# DAP_Main.net
KiCad netlist of a schematic drawn in Altium Designer
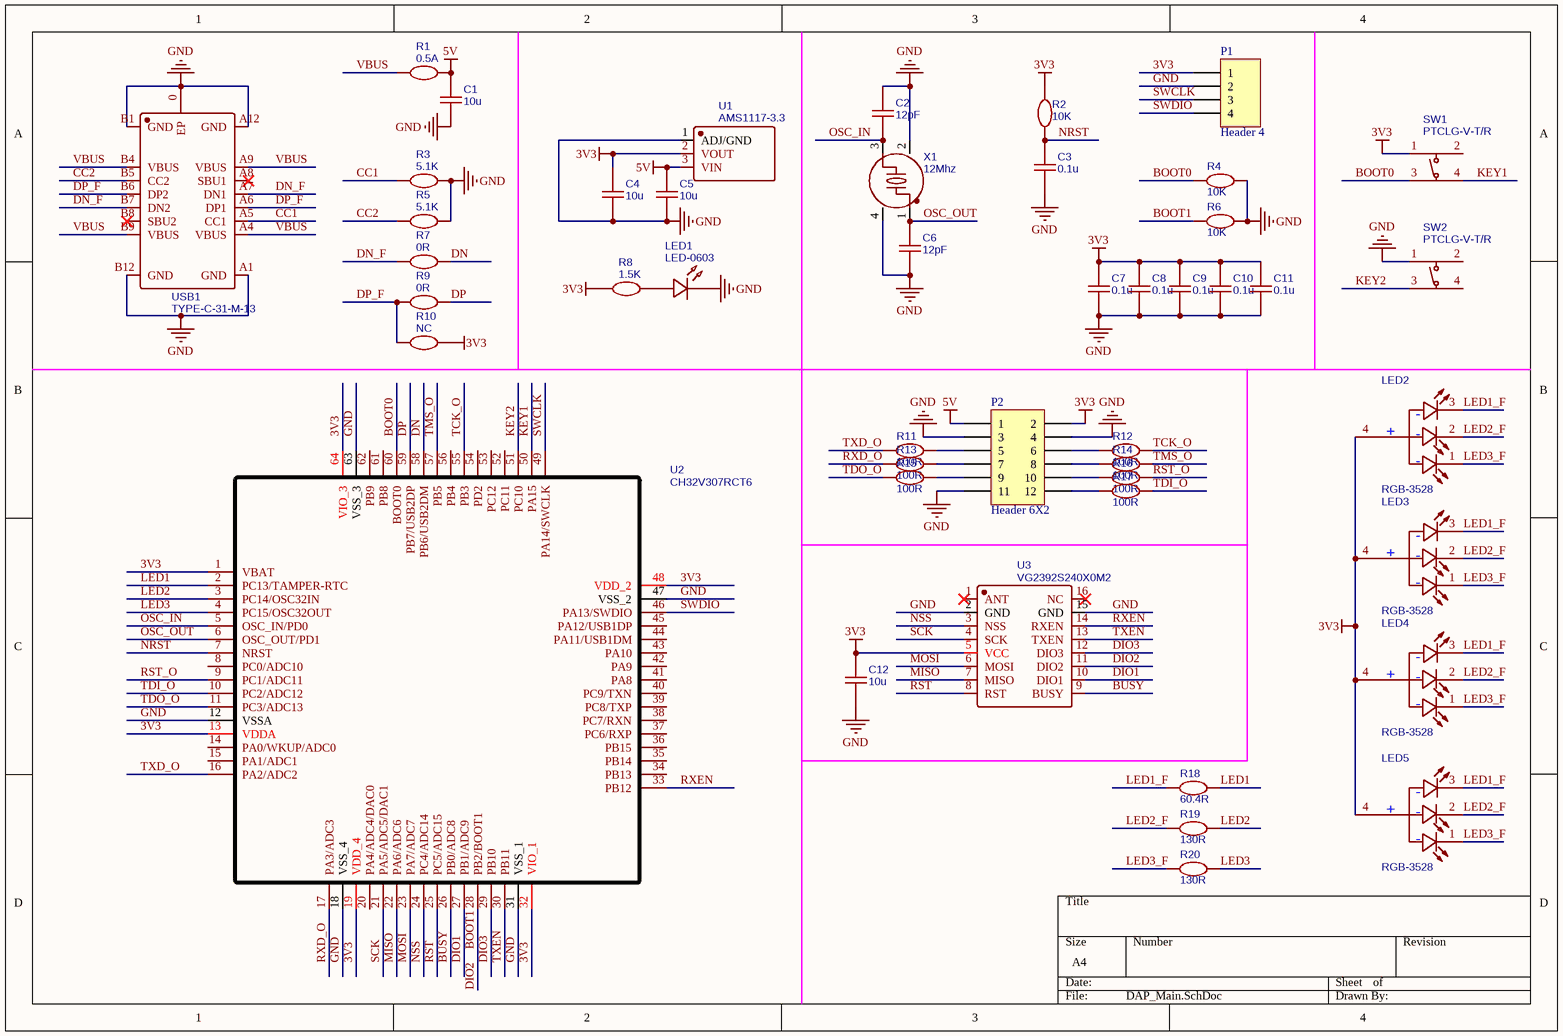
[diagram p0: DAP_Main.SchDoc]

(export (version "E")
  (design (tool "Eeschema 10.0.6"))
  (components
    (comp (ref "C1")
      (value "10u")
      (footprint "0603_CAP")
      (fields (field (name "CONTRIBUTOR") "LCEDA_Lib"))
      (libsource (lib "altium-import") (part "root_1_0.1u_"))
    )
    (comp (ref "C2")
      (value "12pF")
      (footprint "0402_CAP")
      (fields (field (name "CONTRIBUTOR") "LCEDA_Lib"))
      (libsource (lib "altium-import") (part "root_1_0.1u_"))
    )
    (comp (ref "C3")
      (value "0.1u")
      (footprint "0402_CAP")
      (fields (field (name "CONTRIBUTOR") "LCEDA_Lib"))
      (libsource (lib "altium-import") (part "root_3_0.1u_"))
    )
    (comp (ref "C4")
      (value "10u")
      (footprint "0603_CAP")
      (fields (field (name "CONTRIBUTOR") "LCEDA_Lib"))
      (libsource (lib "altium-import") (part "root_3_0.1u_"))
    )
    (comp (ref "C5")
      (value "10u")
      (footprint "0603_CAP")
      (fields (field (name "CONTRIBUTOR") "LCEDA_Lib"))
      (libsource (lib "altium-import") (part "root_1_0.1u_"))
    )
    (comp (ref "C6")
      (value "12pF")
      (footprint "0402_CAP")
      (fields (field (name "CONTRIBUTOR") "LCEDA_Lib"))
      (libsource (lib "altium-import") (part "root_1_0.1u_"))
    )
    (comp (ref "C7")
      (value "0.1u")
      (footprint "0402_CAP")
      (fields (field (name "CONTRIBUTOR") "LCEDA_Lib"))
      (libsource (lib "altium-import") (part "root_3_0.1u_"))
    )
    (comp (ref "C8")
      (value "0.1u")
      (footprint "0402_CAP")
      (fields (field (name "CONTRIBUTOR") "LCEDA_Lib"))
      (libsource (lib "altium-import") (part "root_3_0.1u_"))
    )
    (comp (ref "C9")
      (value "0.1u")
      (footprint "0402_CAP")
      (fields (field (name "CONTRIBUTOR") "LCEDA_Lib"))
      (libsource (lib "altium-import") (part "root_3_0.1u_"))
    )
    (comp (ref "C10")
      (value "0.1u")
      (footprint "0402_CAP")
      (fields (field (name "CONTRIBUTOR") "LCEDA_Lib"))
      (libsource (lib "altium-import") (part "root_3_0.1u_"))
    )
    (comp (ref "C11")
      (value "0.1u")
      (footprint "0402_CAP")
      (fields (field (name "CONTRIBUTOR") "LCEDA_Lib"))
      (libsource (lib "altium-import") (part "root_3_0.1u_"))
    )
    (comp (ref "C12")
      (value "10u")
      (footprint "0603_CAP")
      (fields (field (name "CONTRIBUTOR") "LCEDA_Lib"))
      (libsource (lib "altium-import") (part "root_3_0.1u_"))
    )
    (comp (ref "LED1")
      (value "LED-0603")
      (footprint "LED0603_RED")
      (fields
        (field (name "BOM_MANUFACTURER PART") "19-217/R6C-AL1M2VY/3T")
        (field (name "BOM_SUPPLIER PART") "C72044")
        (field (name "CONTRIBUTOR") "LCEDA_01")
      )
      (libsource (lib "altium-import") (part "root_0_LED-0603_R_"))
    )
    (comp (ref "LED2")
      (value "RGB-3528")
      (footprint "LED-ARRAY-SMD_3528-4P-L3.5-W2.8-TL-RD")
      (fields
        (field (name "BOM_SUPPLIER PART") "C264607")
        (field (name "BOM_MANUFACTURER PART") "67-23/R6GHBHC-B01/2T")
        (field (name "CONTRIBUTOR") "LCSC")
      )
      (libsource (lib "altium-import") (part "root_0_67-23/R6GHBHC-B01/2T_"))
    )
    (comp (ref "LED3")
      (value "RGB-3528")
      (footprint "LED-ARRAY-SMD_3528-4P-L3.5-W2.8-TL-RD")
      (fields
        (field (name "BOM_SUPPLIER PART") "C264607")
        (field (name "BOM_MANUFACTURER PART") "67-23/R6GHBHC-B01/2T")
        (field (name "CONTRIBUTOR") "LCSC")
      )
      (libsource (lib "altium-import") (part "root_0_67-23/R6GHBHC-B01/2T_"))
    )
    (comp (ref "LED4")
      (value "RGB-3528")
      (footprint "LED-ARRAY-SMD_3528-4P-L3.5-W2.8-TL-RD")
      (fields
        (field (name "BOM_SUPPLIER PART") "C264607")
        (field (name "BOM_MANUFACTURER PART") "67-23/R6GHBHC-B01/2T")
        (field (name "CONTRIBUTOR") "LCSC")
      )
      (libsource (lib "altium-import") (part "root_0_67-23/R6GHBHC-B01/2T_"))
    )
    (comp (ref "LED5")
      (value "RGB-3528")
      (footprint "LED-ARRAY-SMD_3528-4P-L3.5-W2.8-TL-RD")
      (fields
        (field (name "BOM_SUPPLIER PART") "C264607")
        (field (name "BOM_MANUFACTURER PART") "67-23/R6GHBHC-B01/2T")
        (field (name "CONTRIBUTOR") "LCSC")
      )
      (libsource (lib "altium-import") (part "root_0_67-23/R6GHBHC-B01/2T_"))
    )
    (comp (ref "P1")
      (value "Header 4")
      (footprint "PAD_2.54_1X4")
      (description "Header, 4-Pin")
      (fields (field (name "PUBLISHER") "Altium Limited"))
      (libsource (lib "Miscellaneous Connectors") (part "Header 4"))
    )
    (comp (ref "P2")
      (value "Header 6X2")
      (footprint "PAD_2.54_2x6_M")
      (description "Header, 6-Pin, Dual row")
      (fields (field (name "PUBLISHER") "Altium Limited"))
      (libsource (lib "Miscellaneous Connectors") (part "Header 6X2"))
    )
    (comp (ref "R1")
      (value "0.5A")
      (footprint "0603_RES")
      (fields (field (name "CONTRIBUTOR") "LCEDA_Lib"))
      (libsource (lib "altium-import") (part "root_0_1k_"))
    )
    (comp (ref "R2")
      (value "10K")
      (footprint "0402_RES")
      (fields (field (name "CONTRIBUTOR") "LCEDA_Lib"))
      (libsource (lib "altium-import") (part "root_1_1k_"))
    )
    (comp (ref "R3")
      (value "5.1K")
      (footprint "0402_RES")
      (fields (field (name "CONTRIBUTOR") "LCEDA_Lib"))
      (libsource (lib "altium-import") (part "root_0_1k_"))
    )
    (comp (ref "R4")
      (value "10K")
      (footprint "0402_RES")
      (fields (field (name "CONTRIBUTOR") "LCEDA_Lib"))
      (libsource (lib "altium-import") (part "root_2_1k_"))
    )
    (comp (ref "R5")
      (value "5.1K")
      (footprint "0402_RES")
      (fields (field (name "CONTRIBUTOR") "LCEDA_Lib"))
      (libsource (lib "altium-import") (part "root_0_1k_"))
    )
    (comp (ref "R6")
      (value "10K")
      (footprint "0402_RES")
      (fields (field (name "CONTRIBUTOR") "LCEDA_Lib"))
      (libsource (lib "altium-import") (part "root_2_1k_"))
    )
    (comp (ref "R7")
      (value "0R")
      (footprint "0402_RES")
      (fields (field (name "CONTRIBUTOR") "LCEDA_Lib"))
      (libsource (lib "altium-import") (part "root_0_1k_"))
    )
    (comp (ref "R8")
      (value "1.5K")
      (footprint "0402_RES")
      (fields (field (name "CONTRIBUTOR") "LCEDA_Lib"))
      (libsource (lib "altium-import") (part "root_0_1k_"))
    )
    (comp (ref "R9")
      (value "0R")
      (footprint "0402_RES")
      (fields (field (name "CONTRIBUTOR") "LCEDA_Lib"))
      (libsource (lib "altium-import") (part "root_0_1k_"))
    )
    (comp (ref "R10")
      (value "NC")
      (footprint "0402_RES")
      (fields (field (name "CONTRIBUTOR") "LCEDA_Lib"))
      (libsource (lib "altium-import") (part "root_0_1k_"))
    )
    (comp (ref "R11")
      (value "100R")
      (footprint "0402_RES")
      (fields (field (name "CONTRIBUTOR") "LCEDA_Lib"))
      (libsource (lib "altium-import") (part "root_0_1k_"))
    )
    (comp (ref "R12")
      (value "100R")
      (footprint "0402_RES")
      (fields (field (name "CONTRIBUTOR") "LCEDA_Lib"))
      (libsource (lib "altium-import") (part "root_0_1k_"))
    )
    (comp (ref "R13")
      (value "100R")
      (footprint "0402_RES")
      (fields (field (name "CONTRIBUTOR") "LCEDA_Lib"))
      (libsource (lib "altium-import") (part "root_0_1k_"))
    )
    (comp (ref "R14")
      (value "100R")
      (footprint "0402_RES")
      (fields (field (name "CONTRIBUTOR") "LCEDA_Lib"))
      (libsource (lib "altium-import") (part "root_0_1k_"))
    )
    (comp (ref "R15")
      (value "100R")
      (footprint "0402_RES")
      (fields (field (name "CONTRIBUTOR") "LCEDA_Lib"))
      (libsource (lib "altium-import") (part "root_0_1k_"))
    )
    (comp (ref "R16")
      (value "100R")
      (footprint "0402_RES")
      (fields (field (name "CONTRIBUTOR") "LCEDA_Lib"))
      (libsource (lib "altium-import") (part "root_0_1k_"))
    )
    (comp (ref "R17")
      (value "100R")
      (footprint "0402_RES")
      (fields (field (name "CONTRIBUTOR") "LCEDA_Lib"))
      (libsource (lib "altium-import") (part "root_0_1k_"))
    )
    (comp (ref "R18")
      (value "60.4R")
      (footprint "0603_RES")
      (fields (field (name "CONTRIBUTOR") "LCEDA_Lib"))
      (libsource (lib "altium-import") (part "root_2_1k_"))
    )
    (comp (ref "R19")
      (value "130R")
      (footprint "0603_RES")
      (fields (field (name "CONTRIBUTOR") "LCEDA_Lib"))
      (libsource (lib "altium-import") (part "root_2_1k_"))
    )
    (comp (ref "R20")
      (value "130R")
      (footprint "0603_RES")
      (fields (field (name "CONTRIBUTOR") "LCEDA_Lib"))
      (libsource (lib "altium-import") (part "root_2_1k_"))
    )
    (comp (ref "SW1")
      (value "PTCLG-V-T/R")
      (footprint "SW-SMD_4P-L4.7-W3.5-P1.70-LS5.9")
      (fields (field (name "BOM_SUPPLIER PART") "C495926") (field (name "CONTRIBUTOR") "LCSC"))
      (libsource (lib "altium-import") (part "root_0_PTCLG-V-T/R_"))
    )
    (comp (ref "SW2")
      (value "PTCLG-V-T/R")
      (footprint "SW-SMD_4P-L4.7-W3.5-P1.70-LS5.9")
      (fields (field (name "BOM_SUPPLIER PART") "C495926") (field (name "CONTRIBUTOR") "LCSC"))
      (libsource (lib "altium-import") (part "root_0_PTCLG-V-T/R_"))
    )
    (comp (ref "U1")
      (value "AMS1117-3.3")
      (footprint "SOT-89-3_L4.5-W2.5-P1.50-LS4.2-BR")
      (fields (field (name "BOM_SUPPLIER PART") "C880752") (field (name "CONTRIBUTOR") "LCSC"))
      (libsource (lib "altium-import") (part "root_0_AMS1117-3.3_"))
    )
    (comp (ref "U2")
      (value "CH32V307RCT6")
      (footprint "CH32V307RCRT6")
      (fields (field (name "CONTRIBUTOR") "lzfii"))
      (libsource (lib "altium-import") (part "root_3_CH32V307RCT6_"))
    )
    (comp (ref "U3")
      (value "VG2392S240X0M2")
      (footprint "WIRELM-SMD_16P-L24.0-W16.0-P2.00_VG2392S240X0M2")
      (fields (field (name "BOM_SUPPLIER PART") "C2976523") (field (name "CONTRIBUTOR") "lcsc"))
      (libsource (lib "altium-import") (part "root_0_VG2392S240X0M2_"))
    )
    (comp (ref "USB1")
      (value "TYPE-C-31-M-13")
      (footprint "USB-C-SMD_TYPE-C-31-M-13")
      (fields (field (name "BOM_SUPPLIER PART") "C223906") (field (name "CONTRIBUTOR") "LCSC"))
      (libsource (lib "altium-import") (part "root_0_TYPE-C-31-M-13_"))
    )
    (comp (ref "X1")
      (value "12Mhz")
      (footprint "XTAL3225")
      (fields
        (field (name "BOM_SUPPLIER PART") "C2682774")
        (field (name "BOM_MANUFACTURER PART") "X32258MSB4SI")
        (field (name "CONTRIBUTOR") "LCSC")
      )
      (libsource (lib "altium-import") (part "root_1_8MHz_"))
    )
  )
  (nets
    (net (code "1") (name "/BOOT0") (class "Default")
      (node (ref "R4") (pin "2") (pinfunction "2_2") (pintype "passive"))
      (node (ref "SW1") (pin "3") (pinfunction "3_3") (pintype "passive"))
      (node (ref "U2") (pin "60") (pinfunction "BOOT0_60") (pintype "passive"))
    )
    (net (code "2") (name "/BOOT1") (class "Default")
      (node (ref "R6") (pin "2") (pinfunction "2_2") (pintype "passive"))
      (node (ref "U2") (pin "28") (pinfunction "PB2/BOOT1_28") (pintype "passive"))
      (node (ref "U3") (pin "11") (pinfunction "DIO2_11") (pintype "passive"))
    )
    (net (code "3") (name "/BUSY") (class "Default")
      (node (ref "U2") (pin "26") (pinfunction "PB0/ADC8_26") (pintype "passive"))
      (node (ref "U3") (pin "9") (pinfunction "BUSY_9") (pintype "passive"))
    )
    (net (code "4") (name "/CC1") (class "Default")
      (node (ref "R3") (pin "1") (pinfunction "1_1") (pintype "passive"))
      (node (ref "USB1") (pin "A5") (pinfunction "CC1_A5") (pintype "passive"))
    )
    (net (code "5") (name "/CC2") (class "Default")
      (node (ref "R5") (pin "1") (pinfunction "1_1") (pintype "passive"))
      (node (ref "USB1") (pin "B5") (pinfunction "CC2_B5") (pintype "passive"))
    )
    (net (code "6") (name "/DIO1") (class "Default")
      (node (ref "U2") (pin "27") (pinfunction "PB1/ADC9_27") (pintype "passive"))
      (node (ref "U3") (pin "10") (pinfunction "DIO1_10") (pintype "passive"))
    )
    (net (code "7") (name "/DIO3") (class "Default")
      (node (ref "U2") (pin "29") (pinfunction "PB10_29") (pintype "passive"))
      (node (ref "U3") (pin "12") (pinfunction "DIO3_12") (pintype "passive"))
    )
    (net (code "8") (name "/DN") (class "Default")
      (node (ref "R7") (pin "2") (pinfunction "2_2") (pintype "passive"))
      (node (ref "U2") (pin "58") (pinfunction "PB6/USB2DM_58") (pintype "passive"))
    )
    (net (code "9") (name "/DN_F") (class "Default")
      (node (ref "R7") (pin "1") (pinfunction "1_1") (pintype "passive"))
      (node (ref "USB1") (pin "A7") (pinfunction "DN1_A7") (pintype "passive"))
      (node (ref "USB1") (pin "B7") (pinfunction "DN2_B7") (pintype "passive"))
    )
    (net (code "10") (name "/DP") (class "Default")
      (node (ref "R9") (pin "2") (pinfunction "2_2") (pintype "passive"))
      (node (ref "U2") (pin "59") (pinfunction "PB7/USB2DP_59") (pintype "passive"))
    )
    (net (code "11") (name "/DP_F") (class "Default")
      (node (ref "R10") (pin "1") (pinfunction "1_1") (pintype "passive"))
      (node (ref "R9") (pin "1") (pinfunction "1_1") (pintype "passive"))
      (node (ref "USB1") (pin "A6") (pinfunction "DP1_A6") (pintype "passive"))
      (node (ref "USB1") (pin "B6") (pinfunction "DP2_B6") (pintype "passive"))
    )
    (net (code "12") (name "/KEY1") (class "Default")
      (node (ref "SW1") (pin "4") (pinfunction "4_4") (pintype "passive"))
      (node (ref "U2") (pin "50") (pinfunction "PA15_50") (pintype "passive"))
    )
    (net (code "13") (name "/KEY2") (class "Default")
      (node (ref "SW2") (pin "3") (pinfunction "3_3") (pintype "passive"))
      (node (ref "U2") (pin "51") (pinfunction "PC10_51") (pintype "passive"))
    )
    (net (code "14") (name "/LED1") (class "Default")
      (node (ref "R18") (pin "1") (pinfunction "1_1") (pintype "passive"))
      (node (ref "U2") (pin "2") (pinfunction "PC13/TAMPER-RTC_2") (pintype "passive"))
    )
    (net (code "15") (name "/LED1_F") (class "Default")
      (node (ref "LED2") (pin "3") (pinfunction "3_3") (pintype "passive"))
      (node (ref "LED3") (pin "3") (pinfunction "3_3") (pintype "passive"))
      (node (ref "LED4") (pin "3") (pinfunction "3_3") (pintype "passive"))
      (node (ref "LED5") (pin "3") (pinfunction "3_3") (pintype "passive"))
      (node (ref "R18") (pin "2") (pinfunction "2_2") (pintype "passive"))
    )
    (net (code "16") (name "/LED2") (class "Default")
      (node (ref "R19") (pin "1") (pinfunction "1_1") (pintype "passive"))
      (node (ref "U2") (pin "3") (pinfunction "PC14/OSC32IN_3") (pintype "passive"))
    )
    (net (code "17") (name "/LED2_F") (class "Default")
      (node (ref "LED2") (pin "2") (pinfunction "2_2") (pintype "passive"))
      (node (ref "LED3") (pin "2") (pinfunction "2_2") (pintype "passive"))
      (node (ref "LED4") (pin "2") (pinfunction "2_2") (pintype "passive"))
      (node (ref "LED5") (pin "2") (pinfunction "2_2") (pintype "passive"))
      (node (ref "R19") (pin "2") (pinfunction "2_2") (pintype "passive"))
    )
    (net (code "18") (name "/LED3") (class "Default")
      (node (ref "R20") (pin "1") (pinfunction "1_1") (pintype "passive"))
      (node (ref "U2") (pin "4") (pinfunction "PC15/OSC32OUT_4") (pintype "passive"))
    )
    (net (code "19") (name "/LED3_F") (class "Default")
      (node (ref "LED2") (pin "1") (pinfunction "1_1") (pintype "passive"))
      (node (ref "LED3") (pin "1") (pinfunction "1_1") (pintype "passive"))
      (node (ref "LED4") (pin "1") (pinfunction "1_1") (pintype "passive"))
      (node (ref "LED5") (pin "1") (pinfunction "1_1") (pintype "passive"))
      (node (ref "R20") (pin "2") (pinfunction "2_2") (pintype "passive"))
    )
    (net (code "20") (name "/MISO") (class "Default")
      (node (ref "U2") (pin "22") (pinfunction "PA6/ADC6_22") (pintype "passive"))
      (node (ref "U3") (pin "7") (pinfunction "MISO_7") (pintype "passive"))
    )
    (net (code "21") (name "/MOSI") (class "Default")
      (node (ref "U2") (pin "23") (pinfunction "PA7/ADC7_23") (pintype "passive"))
      (node (ref "U3") (pin "6") (pinfunction "MOSI_6") (pintype "passive"))
    )
    (net (code "22") (name "/NRST") (class "Default")
      (node (ref "C3") (pin "1") (pinfunction "1_1") (pintype "passive"))
      (node (ref "R2") (pin "1") (pinfunction "1_1") (pintype "passive"))
      (node (ref "U2") (pin "7") (pinfunction "NRST_7") (pintype "passive"))
    )
    (net (code "23") (name "/NSS") (class "Default")
      (node (ref "U2") (pin "24") (pinfunction "PC4/ADC14_24") (pintype "passive"))
      (node (ref "U3") (pin "3") (pinfunction "NSS_3") (pintype "passive"))
    )
    (net (code "24") (name "/OSC_IN") (class "Default")
      (node (ref "C2") (pin "1") (pinfunction "1_1") (pintype "passive"))
      (node (ref "U2") (pin "5") (pinfunction "OSC_IN/PD0_5") (pintype "passive"))
      (node (ref "X1") (pin "3") (pinfunction "3_3") (pintype "passive"))
    )
    (net (code "25") (name "/OSC_OUT") (class "Default")
      (node (ref "C6") (pin "2") (pinfunction "2_2") (pintype "passive"))
      (node (ref "U2") (pin "6") (pinfunction "OSC_OUT/PD1_6") (pintype "passive"))
      (node (ref "X1") (pin "1") (pinfunction "1_1") (pintype "passive"))
    )
    (net (code "26") (name "/RST") (class "Default")
      (node (ref "U2") (pin "25") (pinfunction "PC5/ADC15_25") (pintype "passive"))
      (node (ref "U3") (pin "8") (pinfunction "RST_8") (pintype "passive"))
    )
    (net (code "27") (name "/RST_O") (class "Default")
      (node (ref "R16") (pin "2") (pinfunction "2_2") (pintype "passive"))
      (node (ref "U2") (pin "9") (pinfunction "PC1/ADC11_9") (pintype "passive"))
    )
    (net (code "28") (name "/RXD_O") (class "Default")
      (node (ref "R13") (pin "1") (pinfunction "1_1") (pintype "passive"))
      (node (ref "U2") (pin "17") (pinfunction "PA3/ADC3_17") (pintype "passive"))
    )
    (net (code "29") (name "/RXEN") (class "Default")
      (node (ref "U2") (pin "33") (pinfunction "PB12_33") (pintype "passive"))
      (node (ref "U3") (pin "14") (pinfunction "RXEN_14") (pintype "passive"))
    )
    (net (code "30") (name "/SCK") (class "Default")
      (node (ref "U2") (pin "21") (pinfunction "PA5/ADC5/DAC1_21") (pintype "passive"))
      (node (ref "U3") (pin "4") (pinfunction "SCK_4") (pintype "passive"))
    )
    (net (code "31") (name "/SWCLK") (class "Default")
      (node (ref "P1") (pin "3") (pinfunction "3_3") (pintype "passive"))
      (node (ref "U2") (pin "49") (pinfunction "PA14/SWCLK_49") (pintype "passive"))
    )
    (net (code "32") (name "/SWDIO") (class "Default")
      (node (ref "P1") (pin "4") (pinfunction "4_4") (pintype "passive"))
      (node (ref "U2") (pin "46") (pinfunction "PA13/SWDIO_46") (pintype "passive"))
    )
    (net (code "33") (name "/TCK_O") (class "Default")
      (node (ref "R12") (pin "2") (pinfunction "2_2") (pintype "passive"))
      (node (ref "U2") (pin "55") (pinfunction "PB3_55") (pintype "passive"))
    )
    (net (code "34") (name "/TDI_O") (class "Default")
      (node (ref "R17") (pin "2") (pinfunction "2_2") (pintype "passive"))
      (node (ref "U2") (pin "10") (pinfunction "PC2/ADC12_10") (pintype "passive"))
    )
    (net (code "35") (name "/TDO_O") (class "Default")
      (node (ref "R15") (pin "1") (pinfunction "1_1") (pintype "passive"))
      (node (ref "U2") (pin "11") (pinfunction "PC3/ADC13_11") (pintype "passive"))
    )
    (net (code "36") (name "/TMS_O") (class "Default")
      (node (ref "R14") (pin "2") (pinfunction "2_2") (pintype "passive"))
      (node (ref "U2") (pin "57") (pinfunction "PB5_57") (pintype "passive"))
    )
    (net (code "37") (name "/TXD_O") (class "Default")
      (node (ref "R11") (pin "1") (pinfunction "1_1") (pintype "passive"))
      (node (ref "U2") (pin "16") (pinfunction "PA2/ADC2_16") (pintype "passive"))
    )
    (net (code "38") (name "/TXEN") (class "Default")
      (node (ref "U2") (pin "30") (pinfunction "PB11_30") (pintype "passive"))
      (node (ref "U3") (pin "13") (pinfunction "TXEN_13") (pintype "passive"))
    )
    (net (code "39") (name "/VBUS") (class "Default")
      (node (ref "R1") (pin "1") (pinfunction "1_1") (pintype "passive"))
      (node (ref "USB1") (pin "A4") (pinfunction "VBUS_A4") (pintype "passive"))
      (node (ref "USB1") (pin "A9") (pinfunction "VBUS_A9") (pintype "passive"))
      (node (ref "USB1") (pin "B4") (pinfunction "VBUS_B4") (pintype "passive"))
      (node (ref "USB1") (pin "B9") (pinfunction "VBUS_B9") (pintype "passive"))
    )
    (net (code "40") (name "3V3") (class "Default")
      (node (ref "C10") (pin "1") (pinfunction "1_1") (pintype "passive"))
      (node (ref "C11") (pin "1") (pinfunction "1_1") (pintype "passive"))
      (node (ref "C12") (pin "1") (pinfunction "1_1") (pintype "passive"))
      (node (ref "C4") (pin "1") (pinfunction "1_1") (pintype "passive"))
      (node (ref "C7") (pin "1") (pinfunction "1_1") (pintype "passive"))
      (node (ref "C8") (pin "1") (pinfunction "1_1") (pintype "passive"))
      (node (ref "C9") (pin "1") (pinfunction "1_1") (pintype "passive"))
      (node (ref "LED2") (pin "4") (pinfunction "4_4") (pintype "passive"))
      (node (ref "LED3") (pin "4") (pinfunction "4_4") (pintype "passive"))
      (node (ref "LED4") (pin "4") (pinfunction "4_4") (pintype "passive"))
      (node (ref "LED5") (pin "4") (pinfunction "4_4") (pintype "passive"))
      (node (ref "P1") (pin "1") (pinfunction "1_1") (pintype "passive"))
      (node (ref "P2") (pin "2") (pinfunction "2_2") (pintype "passive"))
      (node (ref "R10") (pin "2") (pinfunction "2_2") (pintype "passive"))
      (node (ref "R2") (pin "2") (pinfunction "2_2") (pintype "passive"))
      (node (ref "R8") (pin "1") (pinfunction "1_1") (pintype "passive"))
      (node (ref "SW1") (pin "1") (pinfunction "1_1") (pintype "passive"))
      (node (ref "U1") (pin "2") (pinfunction "VOUT_2") (pintype "passive"))
      (node (ref "U2") (pin "1") (pinfunction "VBAT_1") (pintype "passive"))
      (node (ref "U2") (pin "13") (pinfunction "VDDA_13") (pintype "passive"))
      (node (ref "U2") (pin "19") (pinfunction "VDD_4_19") (pintype "passive"))
      (node (ref "U2") (pin "32") (pinfunction "VIO_1_32") (pintype "passive"))
      (node (ref "U2") (pin "48") (pinfunction "VDD_2_48") (pintype "passive"))
      (node (ref "U2") (pin "64") (pinfunction "VIO_3_64") (pintype "passive"))
      (node (ref "U3") (pin "5") (pinfunction "VCC_5") (pintype "passive"))
    )
    (net (code "41") (name "5V") (class "Default")
      (node (ref "C1") (pin "2") (pinfunction "2_2") (pintype "passive"))
      (node (ref "C5") (pin "2") (pinfunction "2_2") (pintype "passive"))
      (node (ref "P2") (pin "1") (pinfunction "1_1") (pintype "passive"))
      (node (ref "R1") (pin "2") (pinfunction "2_2") (pintype "passive"))
      (node (ref "U1") (pin "3") (pinfunction "VIN_3") (pintype "passive"))
    )
    (net (code "42") (name "GND") (class "Default")
      (node (ref "C1") (pin "1") (pinfunction "1_1") (pintype "passive"))
      (node (ref "C10") (pin "2") (pinfunction "2_2") (pintype "passive"))
      (node (ref "C11") (pin "2") (pinfunction "2_2") (pintype "passive"))
      (node (ref "C12") (pin "2") (pinfunction "2_2") (pintype "passive"))
      (node (ref "C2") (pin "2") (pinfunction "2_2") (pintype "passive"))
      (node (ref "C3") (pin "2") (pinfunction "2_2") (pintype "passive"))
      (node (ref "C4") (pin "2") (pinfunction "2_2") (pintype "passive"))
      (node (ref "C5") (pin "1") (pinfunction "1_1") (pintype "passive"))
      (node (ref "C6") (pin "1") (pinfunction "1_1") (pintype "passive"))
      (node (ref "C7") (pin "2") (pinfunction "2_2") (pintype "passive"))
      (node (ref "C8") (pin "2") (pinfunction "2_2") (pintype "passive"))
      (node (ref "C9") (pin "2") (pinfunction "2_2") (pintype "passive"))
      (node (ref "LED1") (pin "2") (pinfunction "2_2") (pintype "passive"))
      (node (ref "P1") (pin "2") (pinfunction "2_2") (pintype "passive"))
      (node (ref "P2") (pin "11") (pinfunction "11_11") (pintype "passive"))
      (node (ref "P2") (pin "3") (pinfunction "3_3") (pintype "passive"))
      (node (ref "P2") (pin "4") (pinfunction "4_4") (pintype "passive"))
      (node (ref "R3") (pin "2") (pinfunction "2_2") (pintype "passive"))
      (node (ref "R4") (pin "1") (pinfunction "1_1") (pintype "passive"))
      (node (ref "R5") (pin "2") (pinfunction "2_2") (pintype "passive"))
      (node (ref "R6") (pin "1") (pinfunction "1_1") (pintype "passive"))
      (node (ref "SW2") (pin "1") (pinfunction "1_1") (pintype "passive"))
      (node (ref "U1") (pin "1") (pinfunction "ADJ/GND_1") (pintype "passive"))
      (node (ref "U2") (pin "12") (pinfunction "VSSA_12") (pintype "passive"))
      (node (ref "U2") (pin "18") (pinfunction "VSS_4_18") (pintype "passive"))
      (node (ref "U2") (pin "31") (pinfunction "VSS_1_31") (pintype "passive"))
      (node (ref "U2") (pin "47") (pinfunction "VSS_2_47") (pintype "passive"))
      (node (ref "U2") (pin "63") (pinfunction "VSS_3_63") (pintype "passive"))
      (node (ref "U3") (pin "15") (pinfunction "GND_15") (pintype "passive"))
      (node (ref "U3") (pin "2") (pinfunction "GND_2") (pintype "passive"))
      (node (ref "USB1") (pin "0") (pinfunction "EP_0") (pintype "passive"))
      (node (ref "USB1") (pin "A1") (pinfunction "GND_A1") (pintype "passive"))
      (node (ref "USB1") (pin "A12") (pinfunction "GND_A12") (pintype "passive"))
      (node (ref "USB1") (pin "B1") (pinfunction "GND_B1") (pintype "passive"))
      (node (ref "USB1") (pin "B12") (pinfunction "GND_B12") (pintype "passive"))
      (node (ref "X1") (pin "2") (pinfunction "GND_2") (pintype "passive"))
      (node (ref "X1") (pin "4") (pinfunction "GND_4") (pintype "passive"))
    )
    (net (code "43") (name "Net-(LED1-Pad1)") (class "Default")
      (node (ref "LED1") (pin "1") (pinfunction "1_1") (pintype "passive"))
      (node (ref "R8") (pin "2") (pinfunction "2_2") (pintype "passive"))
    )
    (net (code "44") (name "Net-(P2-Pad5)") (class "Default")
      (node (ref "P2") (pin "5") (pinfunction "5_5") (pintype "passive"))
      (node (ref "R11") (pin "2") (pinfunction "2_2") (pintype "passive"))
    )
    (net (code "45") (name "Net-(P2-Pad6)") (class "Default")
      (node (ref "P2") (pin "6") (pinfunction "6_6") (pintype "passive"))
      (node (ref "R12") (pin "1") (pinfunction "1_1") (pintype "passive"))
    )
    (net (code "46") (name "Net-(P2-Pad7)") (class "Default")
      (node (ref "P2") (pin "7") (pinfunction "7_7") (pintype "passive"))
      (node (ref "R13") (pin "2") (pinfunction "2_2") (pintype "passive"))
    )
    (net (code "47") (name "Net-(P2-Pad8)") (class "Default")
      (node (ref "P2") (pin "8") (pinfunction "8_8") (pintype "passive"))
      (node (ref "R14") (pin "1") (pinfunction "1_1") (pintype "passive"))
    )
    (net (code "48") (name "Net-(P2-Pad9)") (class "Default")
      (node (ref "P2") (pin "9") (pinfunction "9_9") (pintype "passive"))
      (node (ref "R15") (pin "2") (pinfunction "2_2") (pintype "passive"))
    )
    (net (code "49") (name "Net-(P2-Pad10)") (class "Default")
      (node (ref "P2") (pin "10") (pinfunction "10_10") (pintype "passive"))
      (node (ref "R16") (pin "1") (pinfunction "1_1") (pintype "passive"))
    )
    (net (code "50") (name "Net-(P2-Pad12)") (class "Default")
      (node (ref "P2") (pin "12") (pinfunction "12_12") (pintype "passive"))
      (node (ref "R17") (pin "1") (pinfunction "1_1") (pintype "passive"))
    )
    (net (code "51") (name "unconnected-(SW1-Pad2)") (class "Default")
      (node (ref "SW1") (pin "2") (pinfunction "2_2") (pintype "passive"))
    )
    (net (code "52") (name "unconnected-(SW2-Pad2)") (class "Default")
      (node (ref "SW2") (pin "2") (pinfunction "2_2") (pintype "passive"))
    )
    (net (code "53") (name "unconnected-(SW2-Pad4)") (class "Default")
      (node (ref "SW2") (pin "4") (pinfunction "4_4") (pintype "passive"))
    )
    (net (code "54") (name "unconnected-(U2-PA0{slash}WKUP{slash}ADC0-Pad14)") (class "Default")
      (node (ref "U2") (pin "14") (pinfunction "PA0/WKUP/ADC0_14") (pintype "passive"))
    )
    (net (code "55") (name "unconnected-(U2-PA1{slash}ADC1-Pad15)") (class "Default")
      (node (ref "U2") (pin "15") (pinfunction "PA1/ADC1_15") (pintype "passive"))
    )
    (net (code "56") (name "unconnected-(U2-PA4{slash}ADC4{slash}DAC0-Pad20)") (class "Default")
      (node (ref "U2") (pin "20") (pinfunction "PA4/ADC4/DAC0_20") (pintype "passive"))
    )
    (net (code "57") (name "unconnected-(U2-PA8-Pad41)") (class "Default")
      (node (ref "U2") (pin "41") (pinfunction "PA8_41") (pintype "passive"))
    )
    (net (code "58") (name "unconnected-(U2-PA9-Pad42)") (class "Default")
      (node (ref "U2") (pin "42") (pinfunction "PA9_42") (pintype "passive"))
    )
    (net (code "59") (name "unconnected-(U2-PA10-Pad43)") (class "Default")
      (node (ref "U2") (pin "43") (pinfunction "PA10_43") (pintype "passive"))
    )
    (net (code "60") (name "unconnected-(U2-PA11{slash}USB1DM-Pad44)") (class "Default")
      (node (ref "U2") (pin "44") (pinfunction "PA11/USB1DM_44") (pintype "passive"))
    )
    (net (code "61") (name "unconnected-(U2-PA12{slash}USB1DP-Pad45)") (class "Default")
      (node (ref "U2") (pin "45") (pinfunction "PA12/USB1DP_45") (pintype "passive"))
    )
    (net (code "62") (name "unconnected-(U2-PB4-Pad56)") (class "Default")
      (node (ref "U2") (pin "56") (pinfunction "PB4_56") (pintype "passive"))
    )
    (net (code "63") (name "unconnected-(U2-PB8-Pad61)") (class "Default")
      (node (ref "U2") (pin "61") (pinfunction "PB8_61") (pintype "passive"))
    )
    (net (code "64") (name "unconnected-(U2-PB9-Pad62)") (class "Default")
      (node (ref "U2") (pin "62") (pinfunction "PB9_62") (pintype "passive"))
    )
    (net (code "65") (name "unconnected-(U2-PB13-Pad34)") (class "Default")
      (node (ref "U2") (pin "34") (pinfunction "PB13_34") (pintype "passive"))
    )
    (net (code "66") (name "unconnected-(U2-PB14-Pad35)") (class "Default")
      (node (ref "U2") (pin "35") (pinfunction "PB14_35") (pintype "passive"))
    )
    (net (code "67") (name "unconnected-(U2-PB15-Pad36)") (class "Default")
      (node (ref "U2") (pin "36") (pinfunction "PB15_36") (pintype "passive"))
    )
    (net (code "68") (name "unconnected-(U2-PC0{slash}ADC10-Pad8)") (class "Default")
      (node (ref "U2") (pin "8") (pinfunction "PC0/ADC10_8") (pintype "passive"))
    )
    (net (code "69") (name "unconnected-(U2-PC6{slash}RXP-Pad37)") (class "Default")
      (node (ref "U2") (pin "37") (pinfunction "PC6/RXP_37") (pintype "passive"))
    )
    (net (code "70") (name "unconnected-(U2-PC7{slash}RXN-Pad38)") (class "Default")
      (node (ref "U2") (pin "38") (pinfunction "PC7/RXN_38") (pintype "passive"))
    )
    (net (code "71") (name "unconnected-(U2-PC8{slash}TXP-Pad39)") (class "Default")
      (node (ref "U2") (pin "39") (pinfunction "PC8/TXP_39") (pintype "passive"))
    )
    (net (code "72") (name "unconnected-(U2-PC9{slash}TXN-Pad40)") (class "Default")
      (node (ref "U2") (pin "40") (pinfunction "PC9/TXN_40") (pintype "passive"))
    )
    (net (code "73") (name "unconnected-(U2-PC11-Pad52)") (class "Default")
      (node (ref "U2") (pin "52") (pinfunction "PC11_52") (pintype "passive"))
    )
    (net (code "74") (name "unconnected-(U2-PC12-Pad53)") (class "Default")
      (node (ref "U2") (pin "53") (pinfunction "PC12_53") (pintype "passive"))
    )
    (net (code "75") (name "unconnected-(U2-PD2-Pad54)") (class "Default")
      (node (ref "U2") (pin "54") (pinfunction "PD2_54") (pintype "passive"))
    )
    (net (code "76") (name "unconnected-(U3-ANT-Pad1)") (class "Default")
      (node (ref "U3") (pin "1") (pinfunction "ANT_1") (pintype "passive+no_connect"))
    )
    (net (code "77") (name "unconnected-(U3-NC-Pad16)") (class "Default")
      (node (ref "U3") (pin "16") (pinfunction "NC_16") (pintype "passive+no_connect"))
    )
    (net (code "78") (name "unconnected-(USB1-SBU1-PadA8)") (class "Default")
      (node (ref "USB1") (pin "A8") (pinfunction "SBU1_A8") (pintype "passive+no_connect"))
    )
    (net (code "79") (name "unconnected-(USB1-SBU2-PadB8)") (class "Default")
      (node (ref "USB1") (pin "B8") (pinfunction "SBU2_B8") (pintype "passive+no_connect"))
    )
  )
)
